# OptocouplerSchDoc.net
KiCad netlist of a schematic drawn in Altium Designer
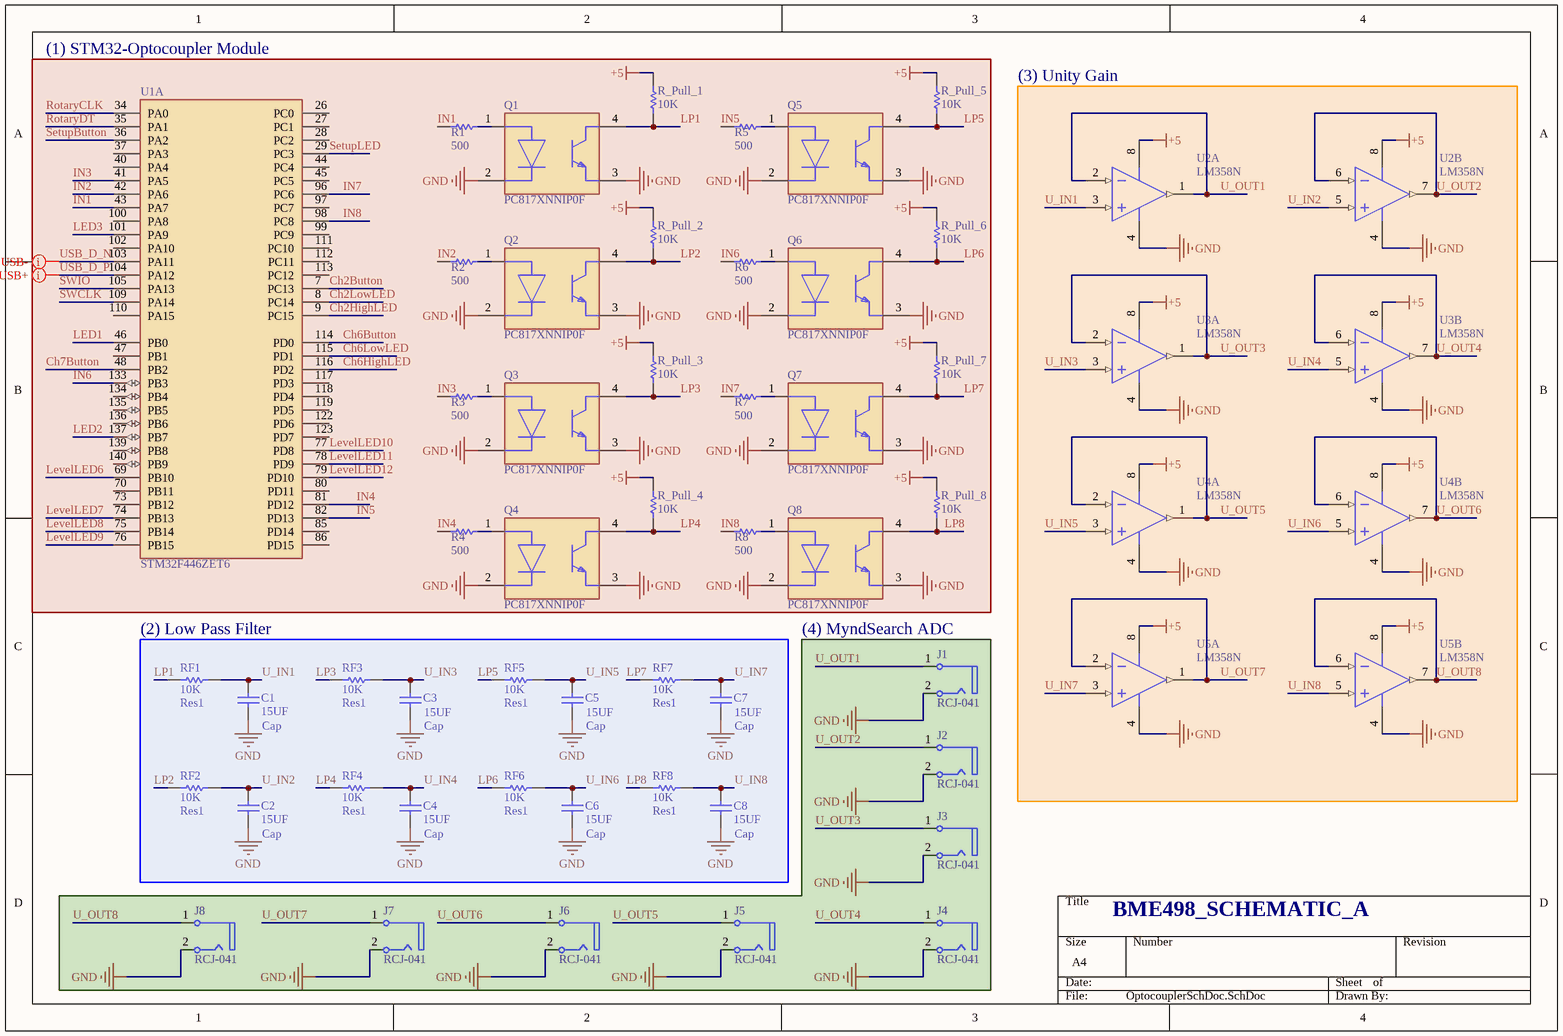
[diagram p0: OptocouplerSchDoc.SchDoc]

(export (version "E")
  (design (tool "Eeschema 10.0.6"))
  (components
    (comp (ref "C1")
      (value "Cap")
      (footprint "RADIAL-0.1")
      (description "Capacitor")
      (fields
        (field (name "ALTIUM_VALUE") "15UF")
        (field (name "MANUFACTURER PART NUMBER") "EEA-GA1C150B")
        (field (name "PUBLISHER") "Altium Limited")
      )
      (libsource (lib "ECE295-Capacitors-TH") (part "CAP ALUM 15UF 20% 16V RADIAL"))
    )
    (comp (ref "C2")
      (value "Cap")
      (footprint "RADIAL-0.1")
      (description "Capacitor")
      (fields
        (field (name "ALTIUM_VALUE") "15UF")
        (field (name "MANUFACTURER PART NUMBER") "EEA-GA1C150B")
        (field (name "PUBLISHER") "Altium Limited")
      )
      (libsource (lib "ECE295-Capacitors-TH") (part "CAP ALUM 15UF 20% 16V RADIAL"))
    )
    (comp (ref "C3")
      (value "Cap")
      (footprint "RADIAL-0.1")
      (description "Capacitor")
      (fields
        (field (name "ALTIUM_VALUE") "15UF")
        (field (name "MANUFACTURER PART NUMBER") "EEA-GA1C150B")
        (field (name "PUBLISHER") "Altium Limited")
      )
      (libsource (lib "ECE295-Capacitors-TH") (part "CAP ALUM 15UF 20% 16V RADIAL"))
    )
    (comp (ref "C4")
      (value "Cap")
      (footprint "RADIAL-0.1")
      (description "Capacitor")
      (fields
        (field (name "ALTIUM_VALUE") "15UF")
        (field (name "MANUFACTURER PART NUMBER") "EEA-GA1C150B")
        (field (name "PUBLISHER") "Altium Limited")
      )
      (libsource (lib "ECE295-Capacitors-TH") (part "CAP ALUM 15UF 20% 16V RADIAL"))
    )
    (comp (ref "C5")
      (value "Cap")
      (footprint "RADIAL-0.1")
      (description "Capacitor")
      (fields
        (field (name "ALTIUM_VALUE") "15UF")
        (field (name "MANUFACTURER PART NUMBER") "EEA-GA1C150B")
        (field (name "PUBLISHER") "Altium Limited")
      )
      (libsource (lib "ECE295-Capacitors-TH") (part "CAP ALUM 15UF 20% 16V RADIAL"))
    )
    (comp (ref "C6")
      (value "Cap")
      (footprint "RADIAL-0.1")
      (description "Capacitor")
      (fields
        (field (name "ALTIUM_VALUE") "15UF")
        (field (name "MANUFACTURER PART NUMBER") "EEA-GA1C150B")
        (field (name "PUBLISHER") "Altium Limited")
      )
      (libsource (lib "ECE295-Capacitors-TH") (part "CAP ALUM 15UF 20% 16V RADIAL"))
    )
    (comp (ref "C7")
      (value "Cap")
      (footprint "RADIAL-0.1")
      (description "Capacitor")
      (fields
        (field (name "ALTIUM_VALUE") "15UF")
        (field (name "MANUFACTURER PART NUMBER") "EEA-GA1C150B")
        (field (name "PUBLISHER") "Altium Limited")
      )
      (libsource (lib "ECE295-Capacitors-TH") (part "CAP ALUM 15UF 20% 16V RADIAL"))
    )
    (comp (ref "C8")
      (value "Cap")
      (footprint "RADIAL-0.1")
      (description "Capacitor")
      (fields
        (field (name "ALTIUM_VALUE") "15UF")
        (field (name "MANUFACTURER PART NUMBER") "EEA-GA1C150B")
        (field (name "PUBLISHER") "Altium Limited")
      )
      (libsource (lib "ECE295-Capacitors-TH") (part "CAP ALUM 15UF 20% 16V RADIAL"))
    )
    (comp (ref "J1")
      (value "RCJ-041")
      (footprint "CUI-RCJ-041_V")
      (description "Female RCJ Jack, 2 Position, Height 11.724 mm, Tail Length 4 mm, RoHS, Bulk")
      (libsource (lib "Altium Content Vault") (part "JACK-2CD2"))
    )
    (comp (ref "J2")
      (value "RCJ-041")
      (footprint "CUI-RCJ-041_V")
      (description "Female RCJ Jack, 2 Position, Height 11.724 mm, Tail Length 4 mm, RoHS, Bulk")
      (libsource (lib "Altium Content Vault") (part "JACK-2CD2"))
    )
    (comp (ref "J3")
      (value "RCJ-041")
      (footprint "CUI-RCJ-041_V")
      (description "Female RCJ Jack, 2 Position, Height 11.724 mm, Tail Length 4 mm, RoHS, Bulk")
      (libsource (lib "Altium Content Vault") (part "JACK-2CD2"))
    )
    (comp (ref "J4")
      (value "RCJ-041")
      (footprint "CUI-RCJ-041_V")
      (description "Female RCJ Jack, 2 Position, Height 11.724 mm, Tail Length 4 mm, RoHS, Bulk")
      (libsource (lib "Altium Content Vault") (part "JACK-2CD2"))
    )
    (comp (ref "J5")
      (value "RCJ-041")
      (footprint "CUI-RCJ-041_V")
      (description "Female RCJ Jack, 2 Position, Height 11.724 mm, Tail Length 4 mm, RoHS, Bulk")
      (libsource (lib "Altium Content Vault") (part "JACK-2CD2"))
    )
    (comp (ref "J6")
      (value "RCJ-041")
      (footprint "CUI-RCJ-041_V")
      (description "Female RCJ Jack, 2 Position, Height 11.724 mm, Tail Length 4 mm, RoHS, Bulk")
      (libsource (lib "Altium Content Vault") (part "JACK-2CD2"))
    )
    (comp (ref "J7")
      (value "RCJ-041")
      (footprint "CUI-RCJ-041_V")
      (description "Female RCJ Jack, 2 Position, Height 11.724 mm, Tail Length 4 mm, RoHS, Bulk")
      (libsource (lib "Altium Content Vault") (part "JACK-2CD2"))
    )
    (comp (ref "J8")
      (value "RCJ-041")
      (footprint "CUI-RCJ-041_V")
      (description "Female RCJ Jack, 2 Position, Height 11.724 mm, Tail Length 4 mm, RoHS, Bulk")
      (libsource (lib "Altium Content Vault") (part "JACK-2CD2"))
    )
    (comp (ref "Q1")
      (value "PC817XNNIP0F")
      (footprint "FP-PC817XNNIP0F-MFG")
      (description "OPTOISOLATOR 5KV TRANS 4SMD")
      (libsource (lib "Altium Content Vault") (part "6470904bf6395c62928ee73e60120b8"))
    )
    (comp (ref "Q2")
      (value "PC817XNNIP0F")
      (footprint "FP-PC817XNNIP0F-MFG")
      (description "OPTOISOLATOR 5KV TRANS 4SMD")
      (libsource (lib "Altium Content Vault") (part "6470904bf6395c62928ee73e60120b8"))
    )
    (comp (ref "Q3")
      (value "PC817XNNIP0F")
      (footprint "FP-PC817XNNIP0F-MFG")
      (description "OPTOISOLATOR 5KV TRANS 4SMD")
      (libsource (lib "Altium Content Vault") (part "6470904bf6395c62928ee73e60120b8"))
    )
    (comp (ref "Q4")
      (value "PC817XNNIP0F")
      (footprint "FP-PC817XNNIP0F-MFG")
      (description "OPTOISOLATOR 5KV TRANS 4SMD")
      (libsource (lib "Altium Content Vault") (part "6470904bf6395c62928ee73e60120b8"))
    )
    (comp (ref "Q5")
      (value "PC817XNNIP0F")
      (footprint "FP-PC817XNNIP0F-MFG")
      (description "OPTOISOLATOR 5KV TRANS 4SMD")
      (libsource (lib "Altium Content Vault") (part "6470904bf6395c62928ee73e60120b8"))
    )
    (comp (ref "Q6")
      (value "PC817XNNIP0F")
      (footprint "FP-PC817XNNIP0F-MFG")
      (description "OPTOISOLATOR 5KV TRANS 4SMD")
      (libsource (lib "Altium Content Vault") (part "6470904bf6395c62928ee73e60120b8"))
    )
    (comp (ref "Q7")
      (value "PC817XNNIP0F")
      (footprint "FP-PC817XNNIP0F-MFG")
      (description "OPTOISOLATOR 5KV TRANS 4SMD")
      (libsource (lib "Altium Content Vault") (part "6470904bf6395c62928ee73e60120b8"))
    )
    (comp (ref "Q8")
      (value "PC817XNNIP0F")
      (footprint "FP-PC817XNNIP0F-MFG")
      (description "OPTOISOLATOR 5KV TRANS 4SMD")
      (libsource (lib "Altium Content Vault") (part "6470904bf6395c62928ee73e60120b8"))
    )
    (comp (ref "R1")
      (value "500")
      (footprint "RESC2013X60X35ML10T20")
      (description "Chip Resistor, 1 KOhm, +/- 1%, 125 mW, -55 to 155 degC, 0805 (2012 Metric), RoHS, Tape and Reel")
      (fields (field (name "TOLERANCE") "1%") (field (name "MANUFACTURER") "Yageo"))
      (libsource (lib "Altium Content Vault") (part "RES-2"))
    )
    (comp (ref "R2")
      (value "500")
      (footprint "RESC2013X60X35ML10T20")
      (description "Chip Resistor, 1 KOhm, +/- 1%, 125 mW, -55 to 155 degC, 0805 (2012 Metric), RoHS, Tape and Reel")
      (fields (field (name "TOLERANCE") "1%") (field (name "MANUFACTURER") "Yageo"))
      (libsource (lib "Altium Content Vault") (part "RES-2"))
    )
    (comp (ref "R3")
      (value "500")
      (footprint "RESC2013X60X35ML10T20")
      (description "Chip Resistor, 1 KOhm, +/- 1%, 125 mW, -55 to 155 degC, 0805 (2012 Metric), RoHS, Tape and Reel")
      (fields (field (name "TOLERANCE") "1%") (field (name "MANUFACTURER") "Yageo"))
      (libsource (lib "Altium Content Vault") (part "RES-2"))
    )
    (comp (ref "R4")
      (value "500")
      (footprint "RESC2013X60X35ML10T20")
      (description "Chip Resistor, 1 KOhm, +/- 1%, 125 mW, -55 to 155 degC, 0805 (2012 Metric), RoHS, Tape and Reel")
      (fields (field (name "TOLERANCE") "1%") (field (name "MANUFACTURER") "Yageo"))
      (libsource (lib "Altium Content Vault") (part "RES-2"))
    )
    (comp (ref "R5")
      (value "500")
      (footprint "RESC2013X60X35ML10T20")
      (description "Chip Resistor, 1 KOhm, +/- 1%, 125 mW, -55 to 155 degC, 0805 (2012 Metric), RoHS, Tape and Reel")
      (fields (field (name "TOLERANCE") "1%") (field (name "MANUFACTURER") "Yageo"))
      (libsource (lib "Altium Content Vault") (part "RES-2"))
    )
    (comp (ref "R6")
      (value "500")
      (footprint "RESC2013X60X35ML10T20")
      (description "Chip Resistor, 1 KOhm, +/- 1%, 125 mW, -55 to 155 degC, 0805 (2012 Metric), RoHS, Tape and Reel")
      (fields (field (name "TOLERANCE") "1%") (field (name "MANUFACTURER") "Yageo"))
      (libsource (lib "Altium Content Vault") (part "RES-2"))
    )
    (comp (ref "R7")
      (value "500")
      (footprint "RESC2013X60X35ML10T20")
      (description "Chip Resistor, 1 KOhm, +/- 1%, 125 mW, -55 to 155 degC, 0805 (2012 Metric), RoHS, Tape and Reel")
      (fields (field (name "TOLERANCE") "1%") (field (name "MANUFACTURER") "Yageo"))
      (libsource (lib "Altium Content Vault") (part "RES-2"))
    )
    (comp (ref "R8")
      (value "500")
      (footprint "RESC2013X60X35ML10T20")
      (description "Chip Resistor, 1 KOhm, +/- 1%, 125 mW, -55 to 155 degC, 0805 (2012 Metric), RoHS, Tape and Reel")
      (fields (field (name "TOLERANCE") "1%") (field (name "MANUFACTURER") "Yageo"))
      (libsource (lib "Altium Content Vault") (part "RES-2"))
    )
    (comp (ref "RF1")
      (value "Res1")
      (footprint "AXIAL-0.3")
      (description "Resistor")
      (fields
        (field (name "ALTIUM_VALUE") "10K")
        (field (name "MANUFACTURER PART NUMBER") "CFR-25JB-52-10K")
        (field (name "TOLERANCE") "0.05")
        (field (name "PUBLISHER") "Altium Limited")
      )
      (libsource (lib "ECE295-Resistors-TH") (part "RES 10K OHM 5% 1/4W AXIAL"))
    )
    (comp (ref "RF2")
      (value "Res1")
      (footprint "AXIAL-0.3")
      (description "Resistor")
      (fields
        (field (name "ALTIUM_VALUE") "10K")
        (field (name "MANUFACTURER PART NUMBER") "CFR-25JB-52-10K")
        (field (name "TOLERANCE") "0.05")
        (field (name "PUBLISHER") "Altium Limited")
      )
      (libsource (lib "ECE295-Resistors-TH") (part "RES 10K OHM 5% 1/4W AXIAL"))
    )
    (comp (ref "RF3")
      (value "Res1")
      (footprint "AXIAL-0.3")
      (description "Resistor")
      (fields
        (field (name "ALTIUM_VALUE") "10K")
        (field (name "MANUFACTURER PART NUMBER") "CFR-25JB-52-10K")
        (field (name "TOLERANCE") "0.05")
        (field (name "PUBLISHER") "Altium Limited")
      )
      (libsource (lib "ECE295-Resistors-TH") (part "RES 10K OHM 5% 1/4W AXIAL"))
    )
    (comp (ref "RF4")
      (value "Res1")
      (footprint "AXIAL-0.3")
      (description "Resistor")
      (fields
        (field (name "ALTIUM_VALUE") "10K")
        (field (name "MANUFACTURER PART NUMBER") "CFR-25JB-52-10K")
        (field (name "TOLERANCE") "0.05")
        (field (name "PUBLISHER") "Altium Limited")
      )
      (libsource (lib "ECE295-Resistors-TH") (part "RES 10K OHM 5% 1/4W AXIAL"))
    )
    (comp (ref "RF5")
      (value "Res1")
      (footprint "AXIAL-0.3")
      (description "Resistor")
      (fields
        (field (name "ALTIUM_VALUE") "10K")
        (field (name "MANUFACTURER PART NUMBER") "CFR-25JB-52-10K")
        (field (name "TOLERANCE") "0.05")
        (field (name "PUBLISHER") "Altium Limited")
      )
      (libsource (lib "ECE295-Resistors-TH") (part "RES 10K OHM 5% 1/4W AXIAL"))
    )
    (comp (ref "RF6")
      (value "Res1")
      (footprint "AXIAL-0.3")
      (description "Resistor")
      (fields
        (field (name "ALTIUM_VALUE") "10K")
        (field (name "MANUFACTURER PART NUMBER") "CFR-25JB-52-10K")
        (field (name "TOLERANCE") "0.05")
        (field (name "PUBLISHER") "Altium Limited")
      )
      (libsource (lib "ECE295-Resistors-TH") (part "RES 10K OHM 5% 1/4W AXIAL"))
    )
    (comp (ref "RF7")
      (value "Res1")
      (footprint "AXIAL-0.3")
      (description "Resistor")
      (fields
        (field (name "ALTIUM_VALUE") "10K")
        (field (name "MANUFACTURER PART NUMBER") "CFR-25JB-52-10K")
        (field (name "TOLERANCE") "0.05")
        (field (name "PUBLISHER") "Altium Limited")
      )
      (libsource (lib "ECE295-Resistors-TH") (part "RES 10K OHM 5% 1/4W AXIAL"))
    )
    (comp (ref "RF8")
      (value "Res1")
      (footprint "AXIAL-0.3")
      (description "Resistor")
      (fields
        (field (name "ALTIUM_VALUE") "10K")
        (field (name "MANUFACTURER PART NUMBER") "CFR-25JB-52-10K")
        (field (name "TOLERANCE") "0.05")
        (field (name "PUBLISHER") "Altium Limited")
      )
      (libsource (lib "ECE295-Resistors-TH") (part "RES 10K OHM 5% 1/4W AXIAL"))
    )
    (comp (ref "R_Pull_1")
      (value "10K")
      (footprint "RESC2013X60X35ML10T20")
      (description "Chip Resistor, 1 KOhm, +/- 1%, 125 mW, -55 to 155 degC, 0805 (2012 Metric), RoHS, Tape and Reel")
      (fields (field (name "TOLERANCE") "1%") (field (name "MANUFACTURER") "Yageo"))
      (libsource (lib "Altium Content Vault") (part "RES-2"))
    )
    (comp (ref "R_Pull_2")
      (value "10K")
      (footprint "RESC2013X60X35ML10T20")
      (description "Chip Resistor, 1 KOhm, +/- 1%, 125 mW, -55 to 155 degC, 0805 (2012 Metric), RoHS, Tape and Reel")
      (fields (field (name "TOLERANCE") "1%") (field (name "MANUFACTURER") "Yageo"))
      (libsource (lib "Altium Content Vault") (part "RES-2"))
    )
    (comp (ref "R_Pull_3")
      (value "10K")
      (footprint "RESC2013X60X35ML10T20")
      (description "Chip Resistor, 1 KOhm, +/- 1%, 125 mW, -55 to 155 degC, 0805 (2012 Metric), RoHS, Tape and Reel")
      (fields (field (name "TOLERANCE") "1%") (field (name "MANUFACTURER") "Yageo"))
      (libsource (lib "Altium Content Vault") (part "RES-2"))
    )
    (comp (ref "R_Pull_4")
      (value "10K")
      (footprint "RESC2013X60X35ML10T20")
      (description "Chip Resistor, 1 KOhm, +/- 1%, 125 mW, -55 to 155 degC, 0805 (2012 Metric), RoHS, Tape and Reel")
      (fields (field (name "TOLERANCE") "1%") (field (name "MANUFACTURER") "Yageo"))
      (libsource (lib "Altium Content Vault") (part "RES-2"))
    )
    (comp (ref "R_Pull_5")
      (value "10K")
      (footprint "RESC2013X60X35ML10T20")
      (description "Chip Resistor, 1 KOhm, +/- 1%, 125 mW, -55 to 155 degC, 0805 (2012 Metric), RoHS, Tape and Reel")
      (fields (field (name "TOLERANCE") "1%") (field (name "MANUFACTURER") "Yageo"))
      (libsource (lib "Altium Content Vault") (part "RES-2"))
    )
    (comp (ref "R_Pull_6")
      (value "10K")
      (footprint "RESC2013X60X35ML10T20")
      (description "Chip Resistor, 1 KOhm, +/- 1%, 125 mW, -55 to 155 degC, 0805 (2012 Metric), RoHS, Tape and Reel")
      (fields (field (name "TOLERANCE") "1%") (field (name "MANUFACTURER") "Yageo"))
      (libsource (lib "Altium Content Vault") (part "RES-2"))
    )
    (comp (ref "R_Pull_7")
      (value "10K")
      (footprint "RESC2013X60X35ML10T20")
      (description "Chip Resistor, 1 KOhm, +/- 1%, 125 mW, -55 to 155 degC, 0805 (2012 Metric), RoHS, Tape and Reel")
      (fields (field (name "TOLERANCE") "1%") (field (name "MANUFACTURER") "Yageo"))
      (libsource (lib "Altium Content Vault") (part "RES-2"))
    )
    (comp (ref "R_Pull_8")
      (value "10K")
      (footprint "RESC2013X60X35ML10T20")
      (description "Chip Resistor, 1 KOhm, +/- 1%, 125 mW, -55 to 155 degC, 0805 (2012 Metric), RoHS, Tape and Reel")
      (fields (field (name "TOLERANCE") "1%") (field (name "MANUFACTURER") "Yageo"))
      (libsource (lib "Altium Content Vault") (part "RES-2"))
    )
    (comp (ref "U1")
      (value "STM32F446ZET6")
      (footprint "FP-STM32F446ZET6-MFG")
      (description "IC MCU 32BIT 512KB FLASH 144LQFP")
      (fields
        (field (name "OCTOPART") "https://octopart.com/stm32f446zet6-stmicroelectronics-52642927")
        (field (name "MANUFACTURER") "STMicroelectronics")
      )
      (libsource (lib "Altium Content Vault") (part "a0fab8d4e0431f78458e0514a03e2d2"))
    )
    (comp (ref "U2")
      (value "LM358N")
      (footprint "ONSC-PDIP-8-626-05_M")
      (description "Single Supply Dual Operational Amplifier, 3 to 32 V, 0 to 70 degC, 8-Pin PDIP, Tube")
      (fields (field (name "MANUFACTURER") "On Semiconductor"))
      (libsource (lib "Altium Content Vault") (part "ONSC-LM358_NCV2904-8"))
    )
    (comp (ref "U3")
      (value "LM358N")
      (footprint "ONSC-PDIP-8-626-05_M")
      (description "Single Supply Dual Operational Amplifier, 3 to 32 V, 0 to 70 degC, 8-Pin PDIP, Tube")
      (fields (field (name "MANUFACTURER") "On Semiconductor"))
      (libsource (lib "Altium Content Vault") (part "ONSC-LM358_NCV2904-8"))
    )
    (comp (ref "U4")
      (value "LM358N")
      (footprint "ONSC-PDIP-8-626-05_M")
      (description "Single Supply Dual Operational Amplifier, 3 to 32 V, 0 to 70 degC, 8-Pin PDIP, Tube")
      (fields (field (name "MANUFACTURER") "On Semiconductor"))
      (libsource (lib "Altium Content Vault") (part "ONSC-LM358_NCV2904-8"))
    )
    (comp (ref "U5")
      (value "LM358N")
      (footprint "ONSC-PDIP-8-626-05_M")
      (description "Single Supply Dual Operational Amplifier, 3 to 32 V, 0 to 70 degC, 8-Pin PDIP, Tube")
      (fields (field (name "MANUFACTURER") "On Semiconductor"))
      (libsource (lib "Altium Content Vault") (part "ONSC-LM358_NCV2904-8"))
    )
  )
  (nets
    (net (code "1") (name "+5") (class "Default")
      (node (ref "R_Pull_1") (pin "2") (pinfunction "2_2") (pintype "passive"))
      (node (ref "R_Pull_2") (pin "2") (pinfunction "2_2") (pintype "passive"))
      (node (ref "R_Pull_3") (pin "2") (pinfunction "2_2") (pintype "passive"))
      (node (ref "R_Pull_4") (pin "2") (pinfunction "2_2") (pintype "passive"))
      (node (ref "R_Pull_5") (pin "2") (pinfunction "2_2") (pintype "passive"))
      (node (ref "R_Pull_6") (pin "2") (pinfunction "2_2") (pintype "passive"))
      (node (ref "R_Pull_7") (pin "2") (pinfunction "2_2") (pintype "passive"))
      (node (ref "R_Pull_8") (pin "2") (pinfunction "2_2") (pintype "passive"))
      (node (ref "U2") (pin "8") (pinfunction "VCC_8") (pintype "power_in"))
      (node (ref "U3") (pin "8") (pinfunction "VCC_8") (pintype "power_in"))
      (node (ref "U4") (pin "8") (pinfunction "VCC_8") (pintype "power_in"))
      (node (ref "U5") (pin "8") (pinfunction "VCC_8") (pintype "power_in"))
    )
    (net (code "2") (name "/Ch2Button") (class "Default")
      (node (ref "U1") (pin "7") (pinfunction "PC13_7") (pintype "passive"))
    )
    (net (code "3") (name "/Ch2HighLED") (class "Default")
      (node (ref "U1") (pin "9") (pinfunction "PC15_9") (pintype "passive"))
    )
    (net (code "4") (name "/Ch2LowLED") (class "Default")
      (node (ref "U1") (pin "8") (pinfunction "PC14_8") (pintype "passive"))
    )
    (net (code "5") (name "/Ch6Button") (class "Default")
      (node (ref "U1") (pin "114") (pinfunction "PD0_114") (pintype "passive"))
    )
    (net (code "6") (name "/Ch6HighLED") (class "Default")
      (node (ref "U1") (pin "116") (pinfunction "PD2_116") (pintype "passive"))
    )
    (net (code "7") (name "/Ch6LowLED") (class "Default")
      (node (ref "U1") (pin "115") (pinfunction "PD1_115") (pintype "passive"))
    )
    (net (code "8") (name "/Ch7Button") (class "Default")
      (node (ref "U1") (pin "48") (pinfunction "PB2_48") (pintype "passive"))
    )
    (net (code "9") (name "/IN1") (class "Default")
      (node (ref "R1") (pin "1") (pinfunction "1_1") (pintype "passive"))
      (node (ref "U1") (pin "43") (pinfunction "PA7_43") (pintype "passive"))
    )
    (net (code "10") (name "/IN2") (class "Default")
      (node (ref "R2") (pin "1") (pinfunction "1_1") (pintype "passive"))
      (node (ref "U1") (pin "42") (pinfunction "PA6_42") (pintype "passive"))
    )
    (net (code "11") (name "/IN3") (class "Default")
      (node (ref "R3") (pin "1") (pinfunction "1_1") (pintype "passive"))
      (node (ref "U1") (pin "41") (pinfunction "PA5_41") (pintype "passive"))
    )
    (net (code "12") (name "/IN4") (class "Default")
      (node (ref "R4") (pin "1") (pinfunction "1_1") (pintype "passive"))
      (node (ref "U1") (pin "81") (pinfunction "PD12_81") (pintype "passive"))
    )
    (net (code "13") (name "/IN5") (class "Default")
      (node (ref "R5") (pin "1") (pinfunction "1_1") (pintype "passive"))
      (node (ref "U1") (pin "82") (pinfunction "PD13_82") (pintype "passive"))
    )
    (net (code "14") (name "/IN6") (class "Default")
      (node (ref "R6") (pin "1") (pinfunction "1_1") (pintype "passive"))
      (node (ref "U1") (pin "133") (pinfunction "PB3_133") (pintype "bidirectional"))
    )
    (net (code "15") (name "/IN7") (class "Default")
      (node (ref "R7") (pin "1") (pinfunction "1_1") (pintype "passive"))
      (node (ref "U1") (pin "96") (pinfunction "PC6_96") (pintype "passive"))
    )
    (net (code "16") (name "/IN8") (class "Default")
      (node (ref "R8") (pin "1") (pinfunction "1_1") (pintype "passive"))
      (node (ref "U1") (pin "98") (pinfunction "PC8_98") (pintype "passive"))
    )
    (net (code "17") (name "/LED1") (class "Default")
      (node (ref "U1") (pin "46") (pinfunction "PB0_46") (pintype "passive"))
    )
    (net (code "18") (name "/LED2") (class "Default")
      (node (ref "U1") (pin "137") (pinfunction "PB7_137") (pintype "bidirectional"))
    )
    (net (code "19") (name "/LED3") (class "Default")
      (node (ref "U1") (pin "101") (pinfunction "PA9_101") (pintype "passive"))
    )
    (net (code "20") (name "/LP1") (class "Default")
      (node (ref "Q1") (pin "4") (pinfunction "C_4") (pintype "passive"))
      (node (ref "RF1") (pin "1") (pinfunction "1_1") (pintype "passive"))
      (node (ref "R_Pull_1") (pin "1") (pinfunction "1_1") (pintype "passive"))
    )
    (net (code "21") (name "/LP2") (class "Default")
      (node (ref "Q2") (pin "4") (pinfunction "C_4") (pintype "passive"))
      (node (ref "RF2") (pin "1") (pinfunction "1_1") (pintype "passive"))
      (node (ref "R_Pull_2") (pin "1") (pinfunction "1_1") (pintype "passive"))
    )
    (net (code "22") (name "/LP3") (class "Default")
      (node (ref "Q3") (pin "4") (pinfunction "C_4") (pintype "passive"))
      (node (ref "RF3") (pin "1") (pinfunction "1_1") (pintype "passive"))
      (node (ref "R_Pull_3") (pin "1") (pinfunction "1_1") (pintype "passive"))
    )
    (net (code "23") (name "/LP4") (class "Default")
      (node (ref "Q4") (pin "4") (pinfunction "C_4") (pintype "passive"))
      (node (ref "RF4") (pin "1") (pinfunction "1_1") (pintype "passive"))
      (node (ref "R_Pull_4") (pin "1") (pinfunction "1_1") (pintype "passive"))
    )
    (net (code "24") (name "/LP5") (class "Default")
      (node (ref "Q5") (pin "4") (pinfunction "C_4") (pintype "passive"))
      (node (ref "RF5") (pin "1") (pinfunction "1_1") (pintype "passive"))
      (node (ref "R_Pull_5") (pin "1") (pinfunction "1_1") (pintype "passive"))
    )
    (net (code "25") (name "/LP6") (class "Default")
      (node (ref "Q6") (pin "4") (pinfunction "C_4") (pintype "passive"))
      (node (ref "RF6") (pin "1") (pinfunction "1_1") (pintype "passive"))
      (node (ref "R_Pull_6") (pin "1") (pinfunction "1_1") (pintype "passive"))
    )
    (net (code "26") (name "/LP7") (class "Default")
      (node (ref "Q7") (pin "4") (pinfunction "C_4") (pintype "passive"))
      (node (ref "RF7") (pin "1") (pinfunction "1_1") (pintype "passive"))
      (node (ref "R_Pull_7") (pin "1") (pinfunction "1_1") (pintype "passive"))
    )
    (net (code "27") (name "/LP8") (class "Default")
      (node (ref "Q8") (pin "4") (pinfunction "C_4") (pintype "passive"))
      (node (ref "RF8") (pin "1") (pinfunction "1_1") (pintype "passive"))
      (node (ref "R_Pull_8") (pin "1") (pinfunction "1_1") (pintype "passive"))
    )
    (net (code "28") (name "/LevelLED6") (class "Default")
      (node (ref "U1") (pin "69") (pinfunction "PB10_69") (pintype "passive"))
    )
    (net (code "29") (name "/LevelLED7") (class "Default")
      (node (ref "U1") (pin "74") (pinfunction "PB13_74") (pintype "passive"))
    )
    (net (code "30") (name "/LevelLED8") (class "Default")
      (node (ref "U1") (pin "75") (pinfunction "PB14_75") (pintype "passive"))
    )
    (net (code "31") (name "/LevelLED9") (class "Default")
      (node (ref "U1") (pin "76") (pinfunction "PB15_76") (pintype "passive"))
    )
    (net (code "32") (name "/LevelLED10") (class "Default")
      (node (ref "U1") (pin "77") (pinfunction "PD8_77") (pintype "passive"))
    )
    (net (code "33") (name "/LevelLED11") (class "Default")
      (node (ref "U1") (pin "78") (pinfunction "PD9_78") (pintype "passive"))
    )
    (net (code "34") (name "/LevelLED12") (class "Default")
      (node (ref "U1") (pin "79") (pinfunction "PD10_79") (pintype "passive"))
    )
    (net (code "35") (name "/RotaryCLK") (class "Default")
      (node (ref "U1") (pin "34") (pinfunction "PA0_34") (pintype "passive"))
    )
    (net (code "36") (name "/RotaryDT") (class "Default")
      (node (ref "U1") (pin "35") (pinfunction "PA1_35") (pintype "passive"))
    )
    (net (code "37") (name "/SWCLK") (class "Default")
      (node (ref "U1") (pin "109") (pinfunction "PA14_109") (pintype "passive"))
    )
    (net (code "38") (name "/SWIO") (class "Default")
      (node (ref "U1") (pin "105") (pinfunction "PA13_105") (pintype "passive"))
    )
    (net (code "39") (name "/SetupButton") (class "Default")
      (node (ref "U1") (pin "36") (pinfunction "PA2_36") (pintype "passive"))
    )
    (net (code "40") (name "/SetupLED") (class "Default")
      (node (ref "U1") (pin "29") (pinfunction "PC3_29") (pintype "passive"))
    )
    (net (code "41") (name "/USB_D_N") (class "Default")
      (node (ref "U1") (pin "103") (pinfunction "PA11_103") (pintype "passive"))
    )
    (net (code "42") (name "/USB_D_P") (class "Default")
      (node (ref "U1") (pin "104") (pinfunction "PA12_104") (pintype "passive"))
    )
    (net (code "43") (name "/U_IN1") (class "Default")
      (node (ref "C1") (pin "2") (pinfunction "2_2") (pintype "passive"))
      (node (ref "RF1") (pin "2") (pinfunction "2_2") (pintype "passive"))
      (node (ref "U2") (pin "3") (pinfunction "INA+_3") (pintype "input"))
    )
    (net (code "44") (name "/U_IN2") (class "Default")
      (node (ref "C2") (pin "2") (pinfunction "2_2") (pintype "passive"))
      (node (ref "RF2") (pin "2") (pinfunction "2_2") (pintype "passive"))
      (node (ref "U2") (pin "5") (pinfunction "INB+_5") (pintype "input"))
    )
    (net (code "45") (name "/U_IN3") (class "Default")
      (node (ref "C3") (pin "2") (pinfunction "2_2") (pintype "passive"))
      (node (ref "RF3") (pin "2") (pinfunction "2_2") (pintype "passive"))
      (node (ref "U3") (pin "3") (pinfunction "INA+_3") (pintype "input"))
    )
    (net (code "46") (name "/U_IN4") (class "Default")
      (node (ref "C4") (pin "2") (pinfunction "2_2") (pintype "passive"))
      (node (ref "RF4") (pin "2") (pinfunction "2_2") (pintype "passive"))
      (node (ref "U3") (pin "5") (pinfunction "INB+_5") (pintype "input"))
    )
    (net (code "47") (name "/U_IN5") (class "Default")
      (node (ref "C5") (pin "2") (pinfunction "2_2") (pintype "passive"))
      (node (ref "RF5") (pin "2") (pinfunction "2_2") (pintype "passive"))
      (node (ref "U4") (pin "3") (pinfunction "INA+_3") (pintype "input"))
    )
    (net (code "48") (name "/U_IN6") (class "Default")
      (node (ref "C6") (pin "2") (pinfunction "2_2") (pintype "passive"))
      (node (ref "RF6") (pin "2") (pinfunction "2_2") (pintype "passive"))
      (node (ref "U4") (pin "5") (pinfunction "INB+_5") (pintype "input"))
    )
    (net (code "49") (name "/U_IN7") (class "Default")
      (node (ref "C7") (pin "2") (pinfunction "2_2") (pintype "passive"))
      (node (ref "RF7") (pin "2") (pinfunction "2_2") (pintype "passive"))
      (node (ref "U5") (pin "3") (pinfunction "INA+_3") (pintype "input"))
    )
    (net (code "50") (name "/U_IN8") (class "Default")
      (node (ref "C8") (pin "2") (pinfunction "2_2") (pintype "passive"))
      (node (ref "RF8") (pin "2") (pinfunction "2_2") (pintype "passive"))
      (node (ref "U5") (pin "5") (pinfunction "INB+_5") (pintype "input"))
    )
    (net (code "51") (name "/U_OUT1") (class "Default")
      (node (ref "J1") (pin "1") (pinfunction "1_1") (pintype "passive"))
      (node (ref "U2") (pin "1") (pinfunction "OUTA_1") (pintype "output"))
      (node (ref "U2") (pin "2") (pinfunction "INA-_2") (pintype "input"))
    )
    (net (code "52") (name "/U_OUT2") (class "Default")
      (node (ref "J2") (pin "1") (pinfunction "1_1") (pintype "passive"))
      (node (ref "U2") (pin "6") (pinfunction "INB-_6") (pintype "input"))
      (node (ref "U2") (pin "7") (pinfunction "OUTB_7") (pintype "output"))
    )
    (net (code "53") (name "/U_OUT3") (class "Default")
      (node (ref "J3") (pin "1") (pinfunction "1_1") (pintype "passive"))
      (node (ref "U3") (pin "1") (pinfunction "OUTA_1") (pintype "output"))
      (node (ref "U3") (pin "2") (pinfunction "INA-_2") (pintype "input"))
    )
    (net (code "54") (name "/U_OUT4") (class "Default")
      (node (ref "J4") (pin "1") (pinfunction "1_1") (pintype "passive"))
      (node (ref "U3") (pin "6") (pinfunction "INB-_6") (pintype "input"))
      (node (ref "U3") (pin "7") (pinfunction "OUTB_7") (pintype "output"))
    )
    (net (code "55") (name "/U_OUT5") (class "Default")
      (node (ref "J5") (pin "1") (pinfunction "1_1") (pintype "passive"))
      (node (ref "U4") (pin "1") (pinfunction "OUTA_1") (pintype "output"))
      (node (ref "U4") (pin "2") (pinfunction "INA-_2") (pintype "input"))
    )
    (net (code "56") (name "/U_OUT6") (class "Default")
      (node (ref "J6") (pin "1") (pinfunction "1_1") (pintype "passive"))
      (node (ref "U4") (pin "6") (pinfunction "INB-_6") (pintype "input"))
      (node (ref "U4") (pin "7") (pinfunction "OUTB_7") (pintype "output"))
    )
    (net (code "57") (name "/U_OUT7") (class "Default")
      (node (ref "J7") (pin "1") (pinfunction "1_1") (pintype "passive"))
      (node (ref "U5") (pin "1") (pinfunction "OUTA_1") (pintype "output"))
      (node (ref "U5") (pin "2") (pinfunction "INA-_2") (pintype "input"))
    )
    (net (code "58") (name "/U_OUT8") (class "Default")
      (node (ref "J8") (pin "1") (pinfunction "1_1") (pintype "passive"))
      (node (ref "U5") (pin "6") (pinfunction "INB-_6") (pintype "input"))
      (node (ref "U5") (pin "7") (pinfunction "OUTB_7") (pintype "output"))
    )
    (net (code "59") (name "GND") (class "Default")
      (node (ref "C1") (pin "1") (pinfunction "1_1") (pintype "passive"))
      (node (ref "C2") (pin "1") (pinfunction "1_1") (pintype "passive"))
      (node (ref "C3") (pin "1") (pinfunction "1_1") (pintype "passive"))
      (node (ref "C4") (pin "1") (pinfunction "1_1") (pintype "passive"))
      (node (ref "C5") (pin "1") (pinfunction "1_1") (pintype "passive"))
      (node (ref "C6") (pin "1") (pinfunction "1_1") (pintype "passive"))
      (node (ref "C7") (pin "1") (pinfunction "1_1") (pintype "passive"))
      (node (ref "C8") (pin "1") (pinfunction "1_1") (pintype "passive"))
      (node (ref "J1") (pin "2") (pinfunction "2_2") (pintype "passive"))
      (node (ref "J2") (pin "2") (pinfunction "2_2") (pintype "passive"))
      (node (ref "J3") (pin "2") (pinfunction "2_2") (pintype "passive"))
      (node (ref "J4") (pin "2") (pinfunction "2_2") (pintype "passive"))
      (node (ref "J5") (pin "2") (pinfunction "2_2") (pintype "passive"))
      (node (ref "J6") (pin "2") (pinfunction "2_2") (pintype "passive"))
      (node (ref "J7") (pin "2") (pinfunction "2_2") (pintype "passive"))
      (node (ref "J8") (pin "2") (pinfunction "2_2") (pintype "passive"))
      (node (ref "Q1") (pin "2") (pinfunction "C_2") (pintype "passive"))
      (node (ref "Q1") (pin "3") (pinfunction "E_3") (pintype "passive"))
      (node (ref "Q2") (pin "2") (pinfunction "C_2") (pintype "passive"))
      (node (ref "Q2") (pin "3") (pinfunction "E_3") (pintype "passive"))
      (node (ref "Q3") (pin "2") (pinfunction "C_2") (pintype "passive"))
      (node (ref "Q3") (pin "3") (pinfunction "E_3") (pintype "passive"))
      (node (ref "Q4") (pin "2") (pinfunction "C_2") (pintype "passive"))
      (node (ref "Q4") (pin "3") (pinfunction "E_3") (pintype "passive"))
      (node (ref "Q5") (pin "2") (pinfunction "C_2") (pintype "passive"))
      (node (ref "Q5") (pin "3") (pinfunction "E_3") (pintype "passive"))
      (node (ref "Q6") (pin "2") (pinfunction "C_2") (pintype "passive"))
      (node (ref "Q6") (pin "3") (pinfunction "E_3") (pintype "passive"))
      (node (ref "Q7") (pin "2") (pinfunction "C_2") (pintype "passive"))
      (node (ref "Q7") (pin "3") (pinfunction "E_3") (pintype "passive"))
      (node (ref "Q8") (pin "2") (pinfunction "C_2") (pintype "passive"))
      (node (ref "Q8") (pin "3") (pinfunction "E_3") (pintype "passive"))
      (node (ref "U2") (pin "4") (pinfunction "VEE/GND_4") (pintype "power_in"))
      (node (ref "U3") (pin "4") (pinfunction "VEE/GND_4") (pintype "power_in"))
      (node (ref "U4") (pin "4") (pinfunction "VEE/GND_4") (pintype "power_in"))
      (node (ref "U5") (pin "4") (pinfunction "VEE/GND_4") (pintype "power_in"))
    )
    (net (code "60") (name "Net-(Q1-A)") (class "Default")
      (node (ref "Q1") (pin "1") (pinfunction "A_1") (pintype "passive"))
      (node (ref "R1") (pin "2") (pinfunction "2_2") (pintype "passive"))
    )
    (net (code "61") (name "Net-(Q2-A)") (class "Default")
      (node (ref "Q2") (pin "1") (pinfunction "A_1") (pintype "passive"))
      (node (ref "R2") (pin "2") (pinfunction "2_2") (pintype "passive"))
    )
    (net (code "62") (name "Net-(Q3-A)") (class "Default")
      (node (ref "Q3") (pin "1") (pinfunction "A_1") (pintype "passive"))
      (node (ref "R3") (pin "2") (pinfunction "2_2") (pintype "passive"))
    )
    (net (code "63") (name "Net-(Q4-A)") (class "Default")
      (node (ref "Q4") (pin "1") (pinfunction "A_1") (pintype "passive"))
      (node (ref "R4") (pin "2") (pinfunction "2_2") (pintype "passive"))
    )
    (net (code "64") (name "Net-(Q5-A)") (class "Default")
      (node (ref "Q5") (pin "1") (pinfunction "A_1") (pintype "passive"))
      (node (ref "R5") (pin "2") (pinfunction "2_2") (pintype "passive"))
    )
    (net (code "65") (name "Net-(Q6-A)") (class "Default")
      (node (ref "Q6") (pin "1") (pinfunction "A_1") (pintype "passive"))
      (node (ref "R6") (pin "2") (pinfunction "2_2") (pintype "passive"))
    )
    (net (code "66") (name "Net-(Q7-A)") (class "Default")
      (node (ref "Q7") (pin "1") (pinfunction "A_1") (pintype "passive"))
      (node (ref "R7") (pin "2") (pinfunction "2_2") (pintype "passive"))
    )
    (net (code "67") (name "Net-(Q8-A)") (class "Default")
      (node (ref "Q8") (pin "1") (pinfunction "A_1") (pintype "passive"))
      (node (ref "R8") (pin "2") (pinfunction "2_2") (pintype "passive"))
    )
    (net (code "68") (name "unconnected-(U1A-PA3-Pad37)") (class "Default")
      (node (ref "U1") (pin "37") (pinfunction "PA3_37") (pintype "passive"))
    )
    (net (code "69") (name "unconnected-(U1A-PA4-Pad40)") (class "Default")
      (node (ref "U1") (pin "40") (pinfunction "PA4_40") (pintype "passive"))
    )
    (net (code "70") (name "unconnected-(U1A-PA8-Pad100)") (class "Default")
      (node (ref "U1") (pin "100") (pinfunction "PA8_100") (pintype "passive"))
    )
    (net (code "71") (name "unconnected-(U1A-PA10-Pad102)") (class "Default")
      (node (ref "U1") (pin "102") (pinfunction "PA10_102") (pintype "passive"))
    )
    (net (code "72") (name "unconnected-(U1A-PA15-Pad110)") (class "Default")
      (node (ref "U1") (pin "110") (pinfunction "PA15_110") (pintype "passive"))
    )
    (net (code "73") (name "unconnected-(U1A-PB1-Pad47)") (class "Default")
      (node (ref "U1") (pin "47") (pinfunction "PB1_47") (pintype "passive"))
    )
    (net (code "74") (name "unconnected-(U1A-PB4-Pad134)") (class "Default")
      (node (ref "U1") (pin "134") (pinfunction "PB4_134") (pintype "bidirectional"))
    )
    (net (code "75") (name "unconnected-(U1A-PB5-Pad135)") (class "Default")
      (node (ref "U1") (pin "135") (pinfunction "PB5_135") (pintype "bidirectional"))
    )
    (net (code "76") (name "unconnected-(U1A-PB6-Pad136)") (class "Default")
      (node (ref "U1") (pin "136") (pinfunction "PB6_136") (pintype "bidirectional"))
    )
    (net (code "77") (name "unconnected-(U1A-PB8-Pad139)") (class "Default")
      (node (ref "U1") (pin "139") (pinfunction "PB8_139") (pintype "bidirectional"))
    )
    (net (code "78") (name "unconnected-(U1A-PB9-Pad140)") (class "Default")
      (node (ref "U1") (pin "140") (pinfunction "PB9_140") (pintype "bidirectional"))
    )
    (net (code "79") (name "unconnected-(U1A-PB11-Pad70)") (class "Default")
      (node (ref "U1") (pin "70") (pinfunction "PB11_70") (pintype "passive"))
    )
    (net (code "80") (name "unconnected-(U1A-PB12-Pad73)") (class "Default")
      (node (ref "U1") (pin "73") (pinfunction "PB12_73") (pintype "passive"))
    )
    (net (code "81") (name "unconnected-(U1A-PC0-Pad26)") (class "Default")
      (node (ref "U1") (pin "26") (pinfunction "PC0_26") (pintype "passive"))
    )
    (net (code "82") (name "unconnected-(U1A-PC1-Pad27)") (class "Default")
      (node (ref "U1") (pin "27") (pinfunction "PC1_27") (pintype "passive"))
    )
    (net (code "83") (name "unconnected-(U1A-PC2-Pad28)") (class "Default")
      (node (ref "U1") (pin "28") (pinfunction "PC2_28") (pintype "passive"))
    )
    (net (code "84") (name "unconnected-(U1A-PC4-Pad44)") (class "Default")
      (node (ref "U1") (pin "44") (pinfunction "PC4_44") (pintype "passive"))
    )
    (net (code "85") (name "unconnected-(U1A-PC5-Pad45)") (class "Default")
      (node (ref "U1") (pin "45") (pinfunction "PC5_45") (pintype "passive"))
    )
    (net (code "86") (name "unconnected-(U1A-PC7-Pad97)") (class "Default")
      (node (ref "U1") (pin "97") (pinfunction "PC7_97") (pintype "passive"))
    )
    (net (code "87") (name "unconnected-(U1A-PC9-Pad99)") (class "Default")
      (node (ref "U1") (pin "99") (pinfunction "PC9_99") (pintype "passive"))
    )
    (net (code "88") (name "unconnected-(U1A-PC10-Pad111)") (class "Default")
      (node (ref "U1") (pin "111") (pinfunction "PC10_111") (pintype "passive"))
    )
    (net (code "89") (name "unconnected-(U1A-PC11-Pad112)") (class "Default")
      (node (ref "U1") (pin "112") (pinfunction "PC11_112") (pintype "passive"))
    )
    (net (code "90") (name "unconnected-(U1A-PC12-Pad113)") (class "Default")
      (node (ref "U1") (pin "113") (pinfunction "PC12_113") (pintype "passive"))
    )
    (net (code "91") (name "unconnected-(U1A-PD3-Pad117)") (class "Default")
      (node (ref "U1") (pin "117") (pinfunction "PD3_117") (pintype "passive"))
    )
    (net (code "92") (name "unconnected-(U1A-PD4-Pad118)") (class "Default")
      (node (ref "U1") (pin "118") (pinfunction "PD4_118") (pintype "passive"))
    )
    (net (code "93") (name "unconnected-(U1A-PD5-Pad119)") (class "Default")
      (node (ref "U1") (pin "119") (pinfunction "PD5_119") (pintype "passive"))
    )
    (net (code "94") (name "unconnected-(U1A-PD6-Pad122)") (class "Default")
      (node (ref "U1") (pin "122") (pinfunction "PD6_122") (pintype "passive"))
    )
    (net (code "95") (name "unconnected-(U1A-PD7-Pad123)") (class "Default")
      (node (ref "U1") (pin "123") (pinfunction "PD7_123") (pintype "passive"))
    )
    (net (code "96") (name "unconnected-(U1A-PD11-Pad80)") (class "Default")
      (node (ref "U1") (pin "80") (pinfunction "PD11_80") (pintype "passive"))
    )
    (net (code "97") (name "unconnected-(U1A-PD14-Pad85)") (class "Default")
      (node (ref "U1") (pin "85") (pinfunction "PD14_85") (pintype "passive"))
    )
    (net (code "98") (name "unconnected-(U1A-PD15-Pad86)") (class "Default")
      (node (ref "U1") (pin "86") (pinfunction "PD15_86") (pintype "passive"))
    )
  )
)
